# S3_Connectors.net
KiCad netlist of a schematic drawn in Altium Designer
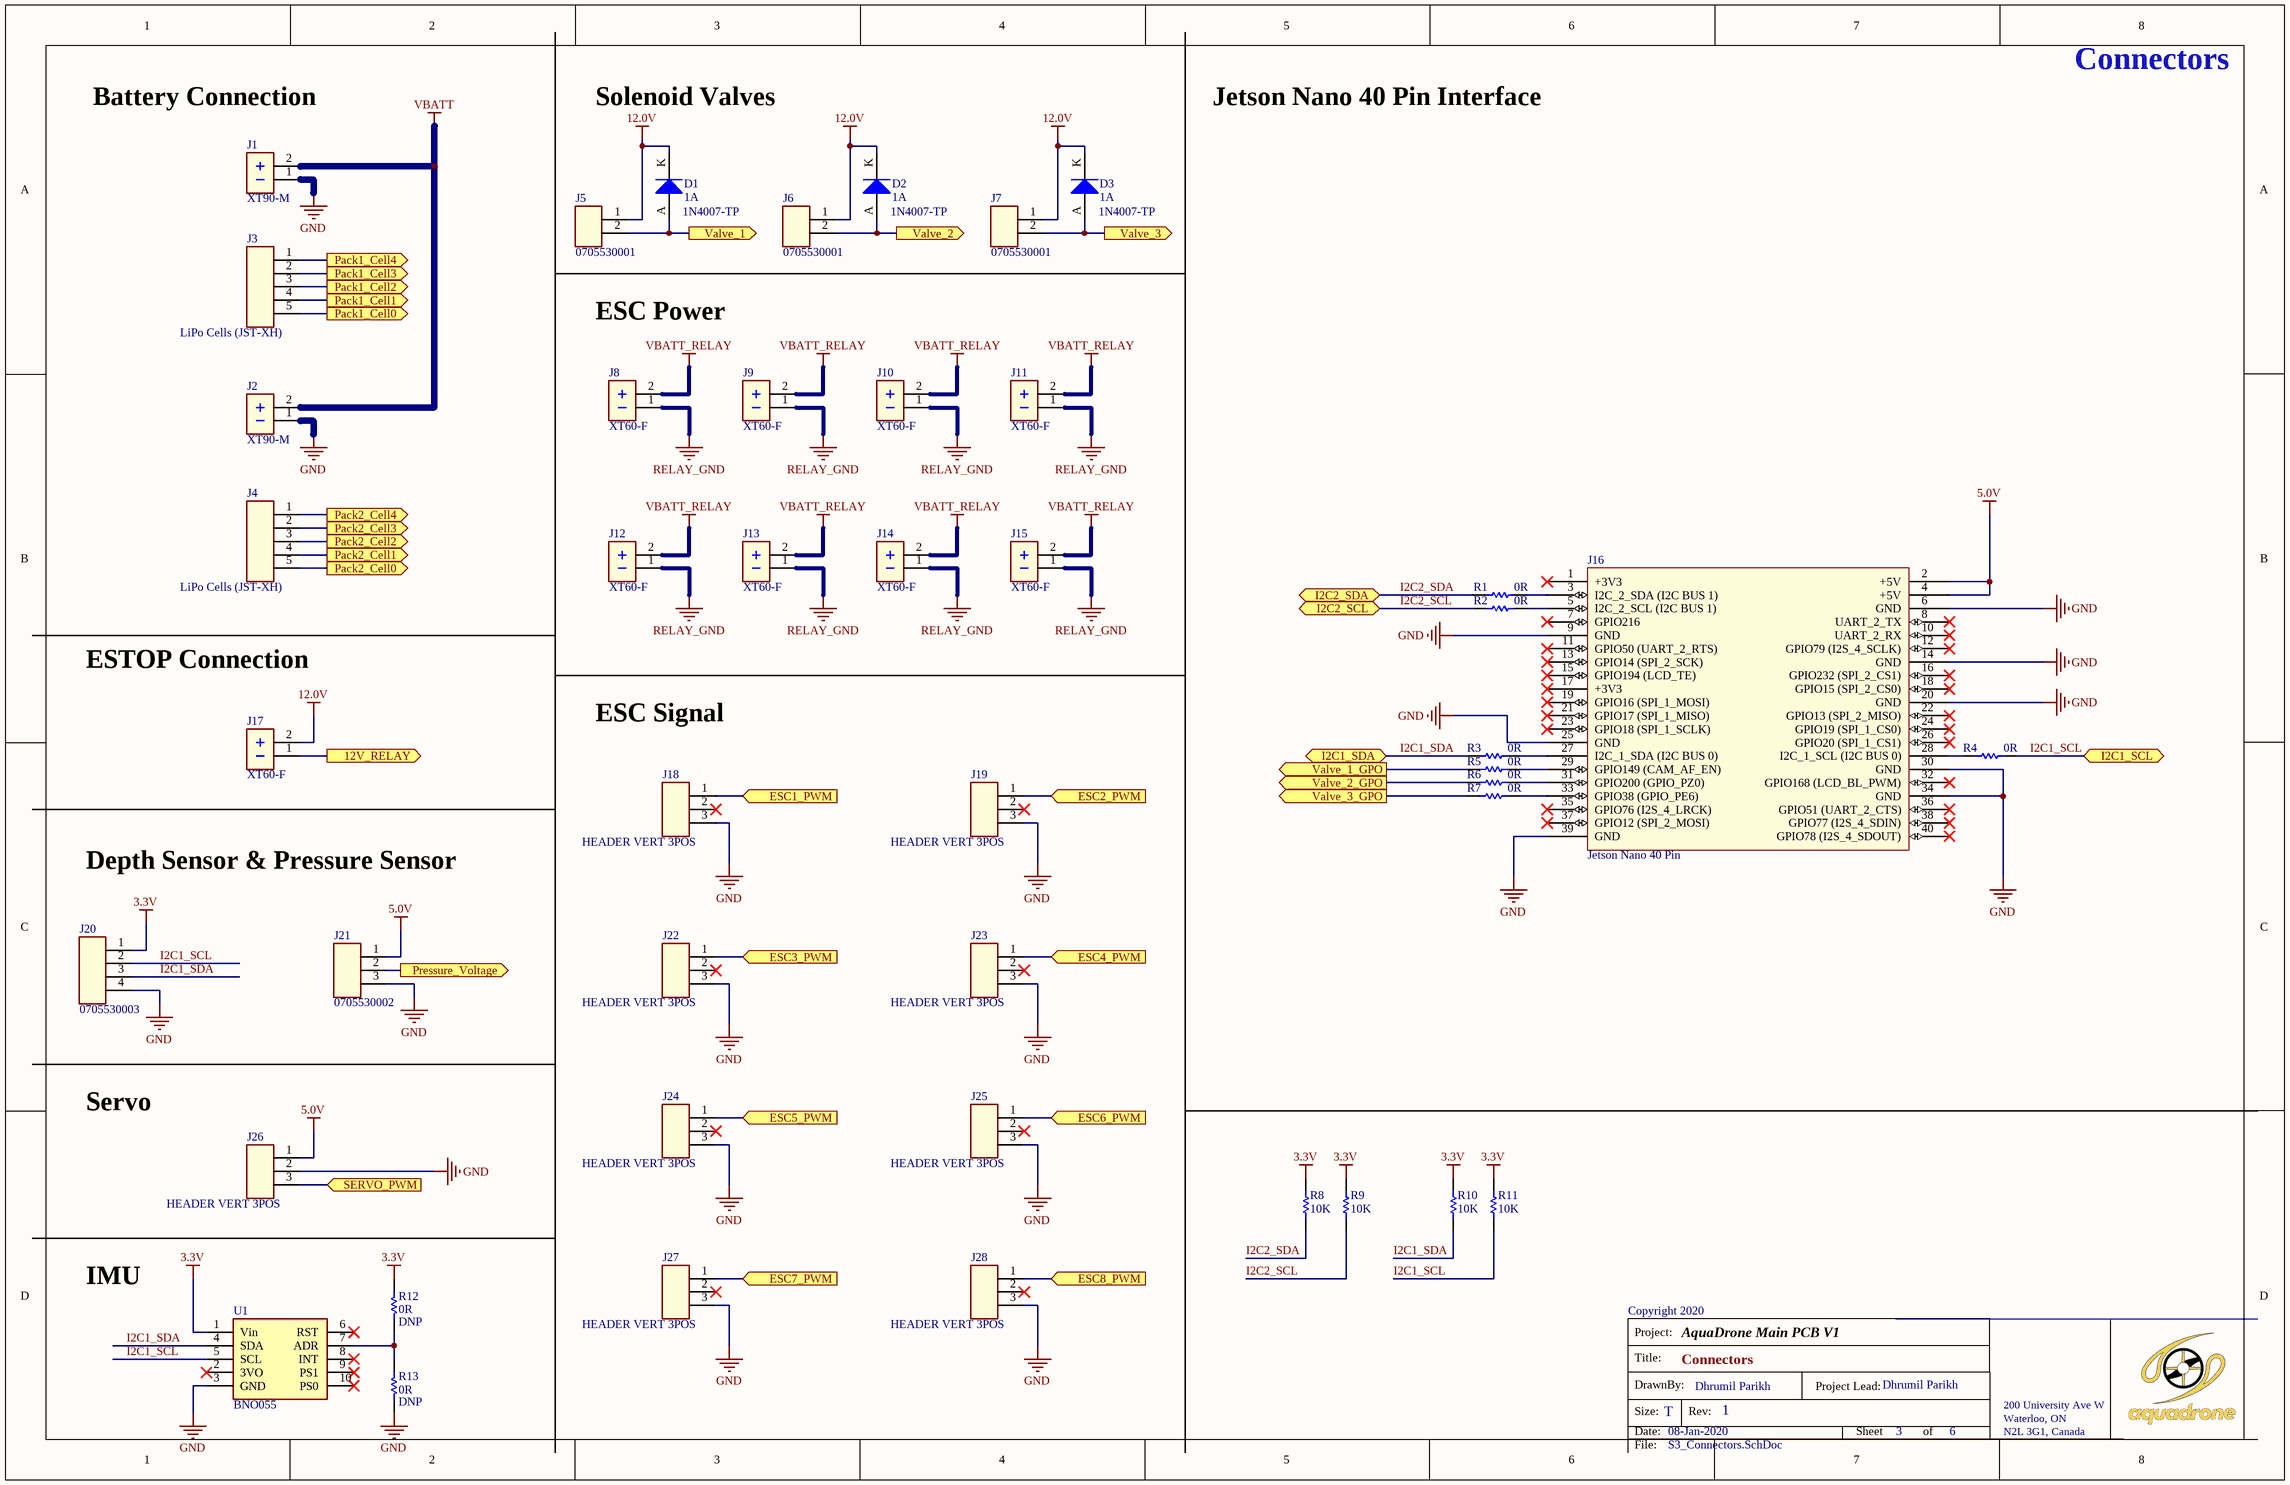
[diagram p0: S3_Connectors.SchDoc]

(export (version "E")
  (design (tool "Eeschema 10.0.6"))
  (components
    (comp (ref "D1")
      (value "1N4007-TP")
      (footprint "DIOAD1405W90L465D235")
      (description "DIODE GEN PURP 1KV 1A DO41")
      (fields (field (name "MFG") "Micro Commercial Co") (field (name "CURRENT") "1A"))
      (libsource (lib "AquaDrone") (part "DIODE GEN PURP 1KV 1A DO41"))
    )
    (comp (ref "D2")
      (value "1N4007-TP")
      (footprint "DIOAD1405W90L465D235")
      (description "DIODE GEN PURP 1KV 1A DO41")
      (fields (field (name "MFG") "Micro Commercial Co") (field (name "CURRENT") "1A"))
      (libsource (lib "AquaDrone") (part "DIODE GEN PURP 1KV 1A DO41"))
    )
    (comp (ref "D3")
      (value "1N4007-TP")
      (footprint "DIOAD1405W90L465D235")
      (description "DIODE GEN PURP 1KV 1A DO41")
      (fields (field (name "MFG") "Micro Commercial Co") (field (name "CURRENT") "1A"))
      (libsource (lib "AquaDrone") (part "DIODE GEN PURP 1KV 1A DO41"))
    )
    (comp (ref "J1")
      (value "XT90-M")
      (footprint "XT90")
      (description "CONN XT90 MALE")
      (fields (field (name "MFG") "DFRobot") (field (name "MFG_PART_NO") "FIT0588"))
      (libsource (lib "AquaDrone") (part "CONN XT90 MALE"))
    )
    (comp (ref "J2")
      (value "XT90-M")
      (footprint "XT90")
      (description "CONN XT90 MALE")
      (fields (field (name "MFG") "DFRobot") (field (name "MFG_PART_NO") "FIT0588"))
      (libsource (lib "AquaDrone") (part "CONN XT90 MALE"))
    )
    (comp (ref "J3")
      (value "LiPo Cells (JST-XH)")
      (footprint "SHDR5W64P0X250_1X5_1490X1150X610P")
      (description "CONN HEADER R/A 5POS 2.5MM")
      (fields (field (name "MFG") "JST Sales America Inc.") (field (name "MFG_PART_NO") "S5B-XH-A(LF)(SN)"))
      (libsource (lib "AquaDrone") (part "CONN HEADER R/A 5POS 2.5MM"))
    )
    (comp (ref "J4")
      (value "LiPo Cells (JST-XH)")
      (footprint "SHDR5W64P0X250_1X5_1490X1150X610P")
      (description "CONN HEADER R/A 5POS 2.5MM")
      (fields (field (name "MFG") "JST Sales America Inc.") (field (name "MFG_PART_NO") "S5B-XH-A(LF)(SN)"))
      (libsource (lib "AquaDrone") (part "CONN HEADER R/A 5POS 2.5MM"))
    )
    (comp (ref "J5")
      (value "0705530001")
      (footprint "SHDRRA2W109P0_254_1X2_762X1359X699P")
      (description "CONN HEADER R/A 2POS 2.54MM")
      (fields (field (name "MFG") "Molex"))
      (libsource (lib "AquaDrone") (part "CONN HEADER R/A 2POS 2.54MM"))
    )
    (comp (ref "J6")
      (value "0705530001")
      (footprint "SHDRRA2W109P0_254_1X2_762X1359X699P")
      (description "CONN HEADER R/A 2POS 2.54MM")
      (fields (field (name "MFG") "Molex"))
      (libsource (lib "AquaDrone") (part "CONN HEADER R/A 2POS 2.54MM"))
    )
    (comp (ref "J7")
      (value "0705530001")
      (footprint "SHDRRA2W109P0_254_1X2_762X1359X699P")
      (description "CONN HEADER R/A 2POS 2.54MM")
      (fields (field (name "MFG") "Molex"))
      (libsource (lib "AquaDrone") (part "CONN HEADER R/A 2POS 2.54MM"))
    )
    (comp (ref "J8")
      (value "XT60-F")
      (footprint "XT60")
      (description "CONN XT60 FEMALE")
      (fields (field (name "MFG") "DFRobot") (field (name "MFG_PART_NO") "FIT0587"))
      (libsource (lib "AquaDrone") (part "CONN XT60 FEMALE"))
    )
    (comp (ref "J9")
      (value "XT60-F")
      (footprint "XT60")
      (description "CONN XT60 FEMALE")
      (fields (field (name "MFG") "DFRobot") (field (name "MFG_PART_NO") "FIT0587"))
      (libsource (lib "AquaDrone") (part "CONN XT60 FEMALE"))
    )
    (comp (ref "J10")
      (value "XT60-F")
      (footprint "XT60")
      (description "CONN XT60 FEMALE")
      (fields (field (name "MFG") "DFRobot") (field (name "MFG_PART_NO") "FIT0587"))
      (libsource (lib "AquaDrone") (part "CONN XT60 FEMALE"))
    )
    (comp (ref "J11")
      (value "XT60-F")
      (footprint "XT60")
      (description "CONN XT60 FEMALE")
      (fields (field (name "MFG") "DFRobot") (field (name "MFG_PART_NO") "FIT0587"))
      (libsource (lib "AquaDrone") (part "CONN XT60 FEMALE"))
    )
    (comp (ref "J12")
      (value "XT60-F")
      (footprint "XT60")
      (description "CONN XT60 FEMALE")
      (fields (field (name "MFG") "DFRobot") (field (name "MFG_PART_NO") "FIT0587"))
      (libsource (lib "AquaDrone") (part "CONN XT60 FEMALE"))
    )
    (comp (ref "J13")
      (value "XT60-F")
      (footprint "XT60")
      (description "CONN XT60 FEMALE")
      (fields (field (name "MFG") "DFRobot") (field (name "MFG_PART_NO") "FIT0587"))
      (libsource (lib "AquaDrone") (part "CONN XT60 FEMALE"))
    )
    (comp (ref "J14")
      (value "XT60-F")
      (footprint "XT60")
      (description "CONN XT60 FEMALE")
      (fields (field (name "MFG") "DFRobot") (field (name "MFG_PART_NO") "FIT0587"))
      (libsource (lib "AquaDrone") (part "CONN XT60 FEMALE"))
    )
    (comp (ref "J15")
      (value "XT60-F")
      (footprint "XT60")
      (description "CONN XT60 FEMALE")
      (fields (field (name "MFG") "DFRobot") (field (name "MFG_PART_NO") "FIT0587"))
      (libsource (lib "AquaDrone") (part "CONN XT60 FEMALE"))
    )
    (comp (ref "J16")
      (value "Jetson Nano 40 Pin")
      (footprint "Jetson Nano")
      (description "Jetson Nano 40 Pin Interface")
      (fields (field (name "MFG") "Jetson") (field (name "MFG_PART_NO") "Nano"))
      (libsource (lib "AquaDrone") (part "Jetson Nano 40 Pin Interface"))
    )
    (comp (ref "J17")
      (value "XT60-F")
      (footprint "XT60")
      (description "CONN XT60 FEMALE")
      (fields (field (name "MFG") "DFRobot") (field (name "MFG_PART_NO") "FIT0587"))
      (libsource (lib "AquaDrone") (part "CONN XT60 FEMALE"))
    )
    (comp (ref "J18")
      (value "HEADER VERT 3POS")
      (footprint "RWMN:61300311121")
      (description "CONN HEADER VERT 3POS 2.54MM")
      (fields (field (name "MFG") "Wurth Electronics Inc.") (field (name "MFG_PART_NO") "61300311121"))
      (libsource (lib "AquaDrone") (part "CONN HEADER VERT 3POS 2.54MM"))
    )
    (comp (ref "J19")
      (value "HEADER VERT 3POS")
      (footprint "RWMN:61300311121")
      (description "CONN HEADER VERT 3POS 2.54MM")
      (fields (field (name "MFG") "Wurth Electronics Inc.") (field (name "MFG_PART_NO") "61300311121"))
      (libsource (lib "AquaDrone") (part "CONN HEADER VERT 3POS 2.54MM"))
    )
    (comp (ref "J20")
      (value "0705530003")
      (footprint "SHDR4W97P0X254_1X4_1271X1359X699P")
      (description "CONN HEADER R/A 4POS 2.54MM")
      (fields (field (name "MFG") "Molex"))
      (libsource (lib "AquaDrone") (part "CONN HEADER R/A 4POS 2.54MM"))
    )
    (comp (ref "J21")
      (value "0705530002")
      (footprint "SHDR3W89P0X254_1X3_1017X1359X699P")
      (description "CONN HEADER R/A 3POS 2.54MM")
      (fields (field (name "MFG") "Molex"))
      (libsource (lib "AquaDrone") (part "CONN HEADER R/A 3POS 2.54MM"))
    )
    (comp (ref "J22")
      (value "HEADER VERT 3POS")
      (footprint "RWMN:61300311121")
      (description "CONN HEADER VERT 3POS 2.54MM")
      (fields (field (name "MFG") "Wurth Electronics Inc.") (field (name "MFG_PART_NO") "61300311121"))
      (libsource (lib "AquaDrone") (part "CONN HEADER VERT 3POS 2.54MM"))
    )
    (comp (ref "J23")
      (value "HEADER VERT 3POS")
      (footprint "RWMN:61300311121")
      (description "CONN HEADER VERT 3POS 2.54MM")
      (fields (field (name "MFG") "Wurth Electronics Inc.") (field (name "MFG_PART_NO") "61300311121"))
      (libsource (lib "AquaDrone") (part "CONN HEADER VERT 3POS 2.54MM"))
    )
    (comp (ref "J24")
      (value "HEADER VERT 3POS")
      (footprint "RWMN:61300311121")
      (description "CONN HEADER VERT 3POS 2.54MM")
      (fields (field (name "MFG") "Wurth Electronics Inc.") (field (name "MFG_PART_NO") "61300311121"))
      (libsource (lib "AquaDrone") (part "CONN HEADER VERT 3POS 2.54MM"))
    )
    (comp (ref "J25")
      (value "HEADER VERT 3POS")
      (footprint "RWMN:61300311121")
      (description "CONN HEADER VERT 3POS 2.54MM")
      (fields (field (name "MFG") "Wurth Electronics Inc.") (field (name "MFG_PART_NO") "61300311121"))
      (libsource (lib "AquaDrone") (part "CONN HEADER VERT 3POS 2.54MM"))
    )
    (comp (ref "J26")
      (value "HEADER VERT 3POS")
      (footprint "RWMN:61300311121")
      (description "CONN HEADER VERT 3POS 2.54MM")
      (fields (field (name "MFG") "Wurth Electronics Inc.") (field (name "MFG_PART_NO") "61300311121"))
      (libsource (lib "AquaDrone") (part "CONN HEADER VERT 3POS 2.54MM"))
    )
    (comp (ref "J27")
      (value "HEADER VERT 3POS")
      (footprint "RWMN:61300311121")
      (description "CONN HEADER VERT 3POS 2.54MM")
      (fields (field (name "MFG") "Wurth Electronics Inc.") (field (name "MFG_PART_NO") "61300311121"))
      (libsource (lib "AquaDrone") (part "CONN HEADER VERT 3POS 2.54MM"))
    )
    (comp (ref "J28")
      (value "HEADER VERT 3POS")
      (footprint "RWMN:61300311121")
      (description "CONN HEADER VERT 3POS 2.54MM")
      (fields (field (name "MFG") "Wurth Electronics Inc.") (field (name "MFG_PART_NO") "61300311121"))
      (libsource (lib "AquaDrone") (part "CONN HEADER VERT 3POS 2.54MM"))
    )
    (comp (ref "R1")
      (value "0R")
      (footprint "RESC2012X07N")
      (description "RES SMD 0 OHM JUMPER 1/8W 0805")
      (fields (field (name "MFG") "Panasonic") (field (name "MFG_PART_NO") "ERJ-6GEY0R00V"))
      (libsource (lib "AquaDrone") (part "RES SMD 0 OHM JUMPER 1/8W 0805"))
    )
    (comp (ref "R2")
      (value "0R")
      (footprint "RESC2012X07N")
      (description "RES SMD 0 OHM JUMPER 1/8W 0805")
      (fields (field (name "MFG") "Panasonic") (field (name "MFG_PART_NO") "ERJ-6GEY0R00V"))
      (libsource (lib "AquaDrone") (part "RES SMD 0 OHM JUMPER 1/8W 0805"))
    )
    (comp (ref "R3")
      (value "0R")
      (footprint "RESC2012X07N")
      (description "RES SMD 0 OHM JUMPER 1/8W 0805")
      (fields (field (name "MFG") "Panasonic") (field (name "MFG_PART_NO") "ERJ-6GEY0R00V"))
      (libsource (lib "AquaDrone") (part "RES SMD 0 OHM JUMPER 1/8W 0805"))
    )
    (comp (ref "R4")
      (value "0R")
      (footprint "RESC2012X07N")
      (description "RES SMD 0 OHM JUMPER 1/8W 0805")
      (fields (field (name "MFG") "Panasonic") (field (name "MFG_PART_NO") "ERJ-6GEY0R00V"))
      (libsource (lib "AquaDrone") (part "RES SMD 0 OHM JUMPER 1/8W 0805"))
    )
    (comp (ref "R5")
      (value "0R")
      (footprint "RESC2012X07N")
      (description "RES SMD 0 OHM JUMPER 1/8W 0805")
      (fields (field (name "MFG") "Panasonic") (field (name "MFG_PART_NO") "ERJ-6GEY0R00V"))
      (libsource (lib "AquaDrone") (part "RES SMD 0 OHM JUMPER 1/8W 0805"))
    )
    (comp (ref "R6")
      (value "0R")
      (footprint "RESC2012X07N")
      (description "RES SMD 0 OHM JUMPER 1/8W 0805")
      (fields (field (name "MFG") "Panasonic") (field (name "MFG_PART_NO") "ERJ-6GEY0R00V"))
      (libsource (lib "AquaDrone") (part "RES SMD 0 OHM JUMPER 1/8W 0805"))
    )
    (comp (ref "R7")
      (value "0R")
      (footprint "RESC2012X07N")
      (description "RES SMD 0 OHM JUMPER 1/8W 0805")
      (fields (field (name "MFG") "Panasonic") (field (name "MFG_PART_NO") "ERJ-6GEY0R00V"))
      (libsource (lib "AquaDrone") (part "RES SMD 0 OHM JUMPER 1/8W 0805"))
    )
    (comp (ref "R8")
      (value "10K")
      (footprint "RESC1608X06N")
      (description "RES SMD 10K OHM 1% 1/10W 0603")
      (fields (field (name "MFG") "Vishay Dale") (field (name "MFG_PART_NO") "CRCW060310K0FKEA"))
      (libsource (lib "AquaDrone") (part "RES SMD 10K OHM 1% 1/10W 0603"))
    )
    (comp (ref "R9")
      (value "10K")
      (footprint "RESC1608X06N")
      (description "RES SMD 10K OHM 1% 1/10W 0603")
      (fields (field (name "MFG") "Vishay Dale") (field (name "MFG_PART_NO") "CRCW060310K0FKEA"))
      (libsource (lib "AquaDrone") (part "RES SMD 10K OHM 1% 1/10W 0603"))
    )
    (comp (ref "R10")
      (value "10K")
      (footprint "RESC1608X06N")
      (description "RES SMD 10K OHM 1% 1/10W 0603")
      (fields (field (name "MFG") "Vishay Dale") (field (name "MFG_PART_NO") "CRCW060310K0FKEA"))
      (libsource (lib "AquaDrone") (part "RES SMD 10K OHM 1% 1/10W 0603"))
    )
    (comp (ref "R11")
      (value "10K")
      (footprint "RESC1608X06N")
      (description "RES SMD 10K OHM 1% 1/10W 0603")
      (fields (field (name "MFG") "Vishay Dale") (field (name "MFG_PART_NO") "CRCW060310K0FKEA"))
      (libsource (lib "AquaDrone") (part "RES SMD 10K OHM 1% 1/10W 0603"))
    )
    (comp (ref "R12")
      (value "0R")
      (footprint "RESC2012X07N")
      (description "RES SMD 0 OHM JUMPER 1/8W 0805")
      (fields
        (field (name "MFG") "Panasonic")
        (field (name "NOSTUFF") "DNP")
        (field (name "MFG_PART_NO") "ERJ-6GEY0R00V")
      )
      (libsource (lib "AquaDrone") (part "RES SMD 0 OHM JUMPER 1/8W 0805"))
    )
    (comp (ref "R13")
      (value "0R")
      (footprint "RESC2012X07N")
      (description "RES SMD 0 OHM JUMPER 1/8W 0805")
      (fields
        (field (name "MFG") "Panasonic")
        (field (name "NOSTUFF") "DNP")
        (field (name "MFG_PART_NO") "ERJ-6GEY0R00V")
      )
      (libsource (lib "AquaDrone") (part "RES SMD 0 OHM JUMPER 1/8W 0805"))
    )
    (comp (ref "U1")
      (value "IC BNO055")
      (footprint "BNO055")
      (fields (field (name "MFG") "Adafruit Industries LLC") (field (name "MFG_PART_NO") "BNO055"))
      (libsource (lib "AquaDrone") (part "IC BNO055"))
    )
  )
  (nets
    (net (code "1") (name "/12V_RELAY") (class "Default") (node (ref "J17") (pin "1") (pintype "passive")))
    (net (code "2") (name "/ESC1_PWM") (class "Default") (node (ref "J18") (pin "1") (pintype "passive")))
    (net (code "3") (name "/ESC2_PWM") (class "Default") (node (ref "J19") (pin "1") (pintype "passive")))
    (net (code "4") (name "/ESC3_PWM") (class "Default") (node (ref "J22") (pin "1") (pintype "passive")))
    (net (code "5") (name "/ESC4_PWM") (class "Default") (node (ref "J23") (pin "1") (pintype "passive")))
    (net (code "6") (name "/ESC5_PWM") (class "Default") (node (ref "J24") (pin "1") (pintype "passive")))
    (net (code "7") (name "/ESC6_PWM") (class "Default") (node (ref "J25") (pin "1") (pintype "passive")))
    (net (code "8") (name "/ESC7_PWM") (class "Default") (node (ref "J27") (pin "1") (pintype "passive")))
    (net (code "9") (name "/ESC8_PWM") (class "Default") (node (ref "J28") (pin "1") (pintype "passive")))
    (net (code "10") (name "/I2C1_SCL") (class "Default")
      (node (ref "J20") (pin "2") (pintype "passive"))
      (node (ref "R11") (pin "1") (pinfunction "1_1") (pintype "passive"))
      (node (ref "R4") (pin "2") (pinfunction "2_2") (pintype "passive"))
      (node (ref "U1") (pin "5") (pinfunction "SCL_5") (pintype "power_in"))
    )
    (net (code "11") (name "/I2C1_SDA") (class "Default")
      (node (ref "J20") (pin "3") (pintype "passive"))
      (node (ref "R10") (pin "1") (pinfunction "1_1") (pintype "passive"))
      (node (ref "R3") (pin "1") (pinfunction "1_1") (pintype "passive"))
      (node (ref "U1") (pin "4") (pinfunction "SDA_4") (pintype "passive"))
    )
    (net (code "12") (name "/I2C2_SCL") (class "Default")
      (node (ref "R2") (pin "1") (pinfunction "1_1") (pintype "passive"))
      (node (ref "R9") (pin "1") (pinfunction "1_1") (pintype "passive"))
    )
    (net (code "13") (name "/I2C2_SDA") (class "Default")
      (node (ref "R1") (pin "1") (pinfunction "1_1") (pintype "passive"))
      (node (ref "R8") (pin "1") (pinfunction "1_1") (pintype "passive"))
    )
    (net (code "14") (name "/Pack1_Cell0") (class "Default") (node (ref "J3") (pin "5") (pintype "passive")))
    (net (code "15") (name "/Pack1_Cell1") (class "Default") (node (ref "J3") (pin "4") (pintype "passive")))
    (net (code "16") (name "/Pack1_Cell2") (class "Default") (node (ref "J3") (pin "3") (pintype "passive")))
    (net (code "17") (name "/Pack1_Cell3") (class "Default") (node (ref "J3") (pin "2") (pintype "passive")))
    (net (code "18") (name "/Pack1_Cell4") (class "Default") (node (ref "J3") (pin "1") (pintype "passive")))
    (net (code "19") (name "/Pack2_Cell0") (class "Default") (node (ref "J4") (pin "5") (pintype "passive")))
    (net (code "20") (name "/Pack2_Cell1") (class "Default") (node (ref "J4") (pin "4") (pintype "passive")))
    (net (code "21") (name "/Pack2_Cell2") (class "Default") (node (ref "J4") (pin "3") (pintype "passive")))
    (net (code "22") (name "/Pack2_Cell3") (class "Default") (node (ref "J4") (pin "2") (pintype "passive")))
    (net (code "23") (name "/Pack2_Cell4") (class "Default") (node (ref "J4") (pin "1") (pintype "passive")))
    (net (code "24") (name "/Pressure_Voltage") (class "Default")
      (node (ref "J21") (pin "2") (pintype "passive"))
    )
    (net (code "25") (name "/SERVO_PWM") (class "Default") (node (ref "J26") (pin "3") (pintype "passive")))
    (net (code "26") (name "/Valve_1") (class "Default")
      (node (ref "D1") (pin "A") (pinfunction "A_A") (pintype "passive"))
      (node (ref "J5") (pin "2") (pintype "passive"))
    )
    (net (code "27") (name "/Valve_1_GPO") (class "Default")
      (node (ref "R5") (pin "1") (pinfunction "1_1") (pintype "passive"))
    )
    (net (code "28") (name "/Valve_2") (class "Default")
      (node (ref "D2") (pin "A") (pinfunction "A_A") (pintype "passive"))
      (node (ref "J6") (pin "2") (pintype "passive"))
    )
    (net (code "29") (name "/Valve_2_GPO") (class "Default")
      (node (ref "R6") (pin "1") (pinfunction "1_1") (pintype "passive"))
    )
    (net (code "30") (name "/Valve_3") (class "Default")
      (node (ref "D3") (pin "A") (pinfunction "A_A") (pintype "passive"))
      (node (ref "J7") (pin "2") (pintype "passive"))
    )
    (net (code "31") (name "/Valve_3_GPO") (class "Default")
      (node (ref "R7") (pin "1") (pinfunction "1_1") (pintype "passive"))
    )
    (net (code "32") (name "3.3V") (class "Default")
      (node (ref "J20") (pin "1") (pintype "passive"))
      (node (ref "R10") (pin "2") (pinfunction "2_2") (pintype "passive"))
      (node (ref "R11") (pin "2") (pinfunction "2_2") (pintype "passive"))
      (node (ref "R12") (pin "1") (pinfunction "1_1") (pintype "passive"))
      (node (ref "R8") (pin "2") (pinfunction "2_2") (pintype "passive"))
      (node (ref "R9") (pin "2") (pinfunction "2_2") (pintype "passive"))
      (node (ref "U1") (pin "1") (pinfunction "Vin_1") (pintype "passive"))
    )
    (net (code "33") (name "5.0V") (class "Default")
      (node (ref "J16") (pin "2") (pinfunction "+5V_2") (pintype "power_in"))
      (node (ref "J16") (pin "4") (pinfunction "+5V_4") (pintype "power_in"))
      (node (ref "J21") (pin "1") (pintype "passive"))
      (node (ref "J26") (pin "1") (pintype "passive"))
    )
    (net (code "34") (name "12.0V") (class "Default")
      (node (ref "D1") (pin "K") (pinfunction "K_K") (pintype "passive"))
      (node (ref "D2") (pin "K") (pinfunction "K_K") (pintype "passive"))
      (node (ref "D3") (pin "K") (pinfunction "K_K") (pintype "passive"))
      (node (ref "J17") (pin "2") (pintype "passive"))
      (node (ref "J5") (pin "1") (pintype "passive"))
      (node (ref "J6") (pin "1") (pintype "passive"))
      (node (ref "J7") (pin "1") (pintype "passive"))
    )
    (net (code "35") (name "GND") (class "Default")
      (node (ref "J1") (pin "1") (pintype "passive"))
      (node (ref "J16") (pin "14") (pinfunction "GND_14") (pintype "power_in"))
      (node (ref "J16") (pin "20") (pinfunction "GND_20") (pintype "power_in"))
      (node (ref "J16") (pin "25") (pinfunction "GND_25") (pintype "power_in"))
      (node (ref "J16") (pin "30") (pinfunction "GND_30") (pintype "power_in"))
      (node (ref "J16") (pin "34") (pinfunction "GND_34") (pintype "passive"))
      (node (ref "J16") (pin "39") (pinfunction "GND_39") (pintype "power_in"))
      (node (ref "J16") (pin "6") (pinfunction "GND_6") (pintype "power_in"))
      (node (ref "J16") (pin "9") (pinfunction "GND_9") (pintype "power_in"))
      (node (ref "J18") (pin "3") (pintype "passive"))
      (node (ref "J19") (pin "3") (pintype "passive"))
      (node (ref "J2") (pin "1") (pintype "passive"))
      (node (ref "J20") (pin "4") (pintype "passive"))
      (node (ref "J21") (pin "3") (pintype "passive"))
      (node (ref "J22") (pin "3") (pintype "passive"))
      (node (ref "J23") (pin "3") (pintype "passive"))
      (node (ref "J24") (pin "3") (pintype "passive"))
      (node (ref "J25") (pin "3") (pintype "passive"))
      (node (ref "J26") (pin "2") (pintype "passive"))
      (node (ref "J27") (pin "3") (pintype "passive"))
      (node (ref "J28") (pin "3") (pintype "passive"))
      (node (ref "R13") (pin "2") (pinfunction "2_2") (pintype "passive"))
      (node (ref "U1") (pin "3") (pinfunction "GND_3") (pintype "passive"))
    )
    (net (code "36") (name "Net-(J16-GPIO38_(GPIO_PE6))") (class "Default")
      (node (ref "J16") (pin "33") (pinfunction "GPIO38_(GPIO_PE6)_33") (pintype "bidirectional"))
      (node (ref "R7") (pin "2") (pinfunction "2_2") (pintype "passive"))
    )
    (net (code "37") (name "Net-(J16-GPIO149_(CAM_AF_EN))") (class "Default")
      (node (ref "J16") (pin "29") (pinfunction "GPIO149_(CAM_AF_EN)_29") (pintype "bidirectional"))
      (node (ref "R5") (pin "2") (pinfunction "2_2") (pintype "passive"))
    )
    (net (code "38") (name "Net-(J16-GPIO200_(GPIO_PZ0))") (class "Default")
      (node (ref "J16") (pin "31") (pinfunction "GPIO200_(GPIO_PZ0)_31") (pintype "bidirectional"))
      (node (ref "R6") (pin "2") (pinfunction "2_2") (pintype "passive"))
    )
    (net (code "39") (name "Net-(J16-I2C_1_SCL_(I2C_BUS_0))") (class "Default")
      (node (ref "J16") (pin "28") (pinfunction "I2C_1_SCL_(I2C_BUS_0)_28") (pintype "passive"))
      (node (ref "R4") (pin "1") (pinfunction "1_1") (pintype "passive"))
    )
    (net (code "40") (name "Net-(J16-I2C_1_SDA_(I2C_BUS_0))") (class "Default")
      (node (ref "J16") (pin "27") (pinfunction "I2C_1_SDA_(I2C_BUS_0)_27") (pintype "passive"))
      (node (ref "R3") (pin "2") (pinfunction "2_2") (pintype "passive"))
    )
    (net (code "41") (name "Net-(J16-I2C_2_SCL_(I2C_BUS_1))") (class "Default")
      (node (ref "J16") (pin "5") (pinfunction "I2C_2_SCL_(I2C_BUS_1)_5") (pintype "bidirectional"))
      (node (ref "R2") (pin "2") (pinfunction "2_2") (pintype "passive"))
    )
    (net (code "42") (name "Net-(J16-I2C_2_SDA_(I2C_BUS_1))") (class "Default")
      (node (ref "J16") (pin "3") (pinfunction "I2C_2_SDA_(I2C_BUS_1)_3") (pintype "bidirectional"))
      (node (ref "R1") (pin "2") (pinfunction "2_2") (pintype "passive"))
    )
    (net (code "43") (name "Net-(U1-ADR)") (class "Default")
      (node (ref "R12") (pin "2") (pinfunction "2_2") (pintype "passive"))
      (node (ref "R13") (pin "1") (pinfunction "1_1") (pintype "passive"))
      (node (ref "U1") (pin "7") (pinfunction "ADR_7") (pintype "passive"))
    )
    (net (code "44") (name "RELAY_GND") (class "Default")
      (node (ref "J10") (pin "1") (pintype "passive"))
      (node (ref "J11") (pin "1") (pintype "passive"))
      (node (ref "J12") (pin "1") (pintype "passive"))
      (node (ref "J13") (pin "1") (pintype "passive"))
      (node (ref "J14") (pin "1") (pintype "passive"))
      (node (ref "J15") (pin "1") (pintype "passive"))
      (node (ref "J8") (pin "1") (pintype "passive"))
      (node (ref "J9") (pin "1") (pintype "passive"))
    )
    (net (code "45") (name "VBATT") (class "Default")
      (node (ref "J1") (pin "2") (pintype "passive"))
      (node (ref "J2") (pin "2") (pintype "passive"))
    )
    (net (code "46") (name "VBATT_RELAY") (class "Default")
      (node (ref "J10") (pin "2") (pintype "passive"))
      (node (ref "J11") (pin "2") (pintype "passive"))
      (node (ref "J12") (pin "2") (pintype "passive"))
      (node (ref "J13") (pin "2") (pintype "passive"))
      (node (ref "J14") (pin "2") (pintype "passive"))
      (node (ref "J15") (pin "2") (pintype "passive"))
      (node (ref "J8") (pin "2") (pintype "passive"))
      (node (ref "J9") (pin "2") (pintype "passive"))
    )
    (net (code "47") (name "unconnected-(J16-+3V3-Pad1)") (class "Default")
      (node (ref "J16") (pin "1") (pinfunction "+3V3_1") (pintype "power_in+no_connect"))
    )
    (net (code "48") (name "unconnected-(J16-+3V3-Pad17)") (class "Default")
      (node (ref "J16") (pin "17") (pinfunction "+3V3_17") (pintype "power_in+no_connect"))
    )
    (net (code "49") (name "unconnected-(J16-GPIO12_(SPI_2_MOSI)-Pad37)") (class "Default")
      (node (ref "J16") (pin "37") (pinfunction "GPIO12_(SPI_2_MOSI)_37") (pintype "bidirectional+no_connect"))
    )
    (net (code "50") (name "unconnected-(J16-GPIO13_(SPI_2_MISO)-Pad22)") (class "Default")
      (node (ref "J16") (pin "22") (pinfunction "GPIO13_(SPI_2_MISO)_22") (pintype "bidirectional+no_connect"))
    )
    (net (code "51") (name "unconnected-(J16-GPIO14_(SPI_2_SCK)-Pad13)") (class "Default")
      (node (ref "J16") (pin "13") (pinfunction "GPIO14_(SPI_2_SCK)_13") (pintype "bidirectional+no_connect"))
    )
    (net (code "52") (name "unconnected-(J16-GPIO15_(SPI_2_CS0)-Pad18)") (class "Default")
      (node (ref "J16") (pin "18") (pinfunction "GPIO15_(SPI_2_CS0)_18") (pintype "bidirectional+no_connect"))
    )
    (net (code "53") (name "unconnected-(J16-GPIO16_(SPI_1_MOSI)-Pad19)") (class "Default")
      (node (ref "J16") (pin "19") (pinfunction "GPIO16_(SPI_1_MOSI)_19") (pintype "bidirectional+no_connect"))
    )
    (net (code "54") (name "unconnected-(J16-GPIO17_(SPI_1_MISO)-Pad21)") (class "Default")
      (node (ref "J16") (pin "21") (pinfunction "GPIO17_(SPI_1_MISO)_21") (pintype "bidirectional+no_connect"))
    )
    (net (code "55") (name "unconnected-(J16-GPIO18_(SPI_1_SCLK)-Pad23)") (class "Default")
      (node (ref "J16") (pin "23") (pinfunction "GPIO18_(SPI_1_SCLK)_23") (pintype "bidirectional+no_connect"))
    )
    (net (code "56") (name "unconnected-(J16-GPIO19_(SPI_1_CS0)-Pad24)") (class "Default")
      (node (ref "J16") (pin "24") (pinfunction "GPIO19_(SPI_1_CS0)_24") (pintype "bidirectional+no_connect"))
    )
    (net (code "57") (name "unconnected-(J16-GPIO20_(SPI_1_CS1)-Pad26)") (class "Default")
      (node (ref "J16") (pin "26") (pinfunction "GPIO20_(SPI_1_CS1)_26") (pintype "bidirectional+no_connect"))
    )
    (net (code "58") (name "unconnected-(J16-GPIO50_(UART_2_RTS)-Pad11)") (class "Default")
      (node (ref "J16") (pin "11") (pinfunction "GPIO50_(UART_2_RTS)_11") (pintype "bidirectional+no_connect"))
    )
    (net (code "59") (name "unconnected-(J16-GPIO51_(UART_2_CTS)-Pad36)") (class "Default")
      (node (ref "J16") (pin "36") (pinfunction "GPIO51_(UART_2_CTS)_36") (pintype "bidirectional+no_connect"))
    )
    (net (code "60") (name "unconnected-(J16-GPIO76_(I2S_4_LRCK)-Pad35)") (class "Default")
      (node (ref "J16") (pin "35") (pinfunction "GPIO76_(I2S_4_LRCK)_35") (pintype "bidirectional+no_connect"))
    )
    (net (code "61") (name "unconnected-(J16-GPIO77_(I2S_4_SDIN)-Pad38)") (class "Default")
      (node (ref "J16") (pin "38") (pinfunction "GPIO77_(I2S_4_SDIN)_38") (pintype "bidirectional+no_connect"))
    )
    (net (code "62") (name "unconnected-(J16-GPIO78_(I2S_4_SDOUT)-Pad40)") (class "Default")
      (node (ref "J16") (pin "40") (pinfunction "GPIO78_(I2S_4_SDOUT)_40") (pintype "bidirectional+no_connect"))
    )
    (net (code "63") (name "unconnected-(J16-GPIO79_(I2S_4_SCLK)-Pad12)") (class "Default")
      (node (ref "J16") (pin "12") (pinfunction "GPIO79_(I2S_4_SCLK)_12") (pintype "bidirectional+no_connect"))
    )
    (net (code "64") (name "unconnected-(J16-GPIO168_(LCD_BL_PWM)-Pad32)") (class "Default")
      (node (ref "J16") (pin "32") (pinfunction "GPIO168_(LCD_BL_PWM)_32") (pintype "bidirectional+no_connect"))
    )
    (net (code "65") (name "unconnected-(J16-GPIO194_(LCD_TE)-Pad15)") (class "Default")
      (node (ref "J16") (pin "15") (pinfunction "GPIO194_(LCD_TE)_15") (pintype "bidirectional+no_connect"))
    )
    (net (code "66") (name "unconnected-(J16-GPIO216-Pad7)") (class "Default")
      (node (ref "J16") (pin "7") (pinfunction "GPIO216_7") (pintype "bidirectional+no_connect"))
    )
    (net (code "67") (name "unconnected-(J16-GPIO232_(SPI_2_CS1)-Pad16)") (class "Default")
      (node (ref "J16") (pin "16") (pinfunction "GPIO232_(SPI_2_CS1)_16") (pintype "bidirectional+no_connect"))
    )
    (net (code "68") (name "unconnected-(J16-UART_2_RX-Pad10)") (class "Default")
      (node (ref "J16") (pin "10") (pinfunction "UART_2_RX_10") (pintype "bidirectional+no_connect"))
    )
    (net (code "69") (name "unconnected-(J16-UART_2_TX-Pad8)") (class "Default")
      (node (ref "J16") (pin "8") (pinfunction "UART_2_TX_8") (pintype "bidirectional+no_connect"))
    )
    (net (code "70") (name "unconnected-(J18-Pad2)") (class "Default")
      (node (ref "J18") (pin "2") (pintype "passive+no_connect"))
    )
    (net (code "71") (name "unconnected-(J19-Pad2)") (class "Default")
      (node (ref "J19") (pin "2") (pintype "passive+no_connect"))
    )
    (net (code "72") (name "unconnected-(J22-Pad2)") (class "Default")
      (node (ref "J22") (pin "2") (pintype "passive+no_connect"))
    )
    (net (code "73") (name "unconnected-(J23-Pad2)") (class "Default")
      (node (ref "J23") (pin "2") (pintype "passive+no_connect"))
    )
    (net (code "74") (name "unconnected-(J24-Pad2)") (class "Default")
      (node (ref "J24") (pin "2") (pintype "passive+no_connect"))
    )
    (net (code "75") (name "unconnected-(J25-Pad2)") (class "Default")
      (node (ref "J25") (pin "2") (pintype "passive+no_connect"))
    )
    (net (code "76") (name "unconnected-(J27-Pad2)") (class "Default")
      (node (ref "J27") (pin "2") (pintype "passive+no_connect"))
    )
    (net (code "77") (name "unconnected-(J28-Pad2)") (class "Default")
      (node (ref "J28") (pin "2") (pintype "passive+no_connect"))
    )
    (net (code "78") (name "unconnected-(U1-3VO-Pad2)") (class "Default")
      (node (ref "U1") (pin "2") (pinfunction "3VO_2") (pintype "passive+no_connect"))
    )
    (net (code "79") (name "unconnected-(U1-INT-Pad8)") (class "Default")
      (node (ref "U1") (pin "8") (pinfunction "INT_8") (pintype "passive+no_connect"))
    )
    (net (code "80") (name "unconnected-(U1-PS0-Pad10)") (class "Default")
      (node (ref "U1") (pin "10") (pinfunction "PS0_10") (pintype "passive+no_connect"))
    )
    (net (code "81") (name "unconnected-(U1-PS1-Pad9)") (class "Default")
      (node (ref "U1") (pin "9") (pinfunction "PS1_9") (pintype "passive+no_connect"))
    )
    (net (code "82") (name "unconnected-(U1-RST-Pad6)") (class "Default")
      (node (ref "U1") (pin "6") (pinfunction "RST_6") (pintype "power_in+no_connect"))
    )
  )
)
